# KP_Fedorov_SM5-71B.net
KiCad netlist of a schematic drawn in Altium Designer
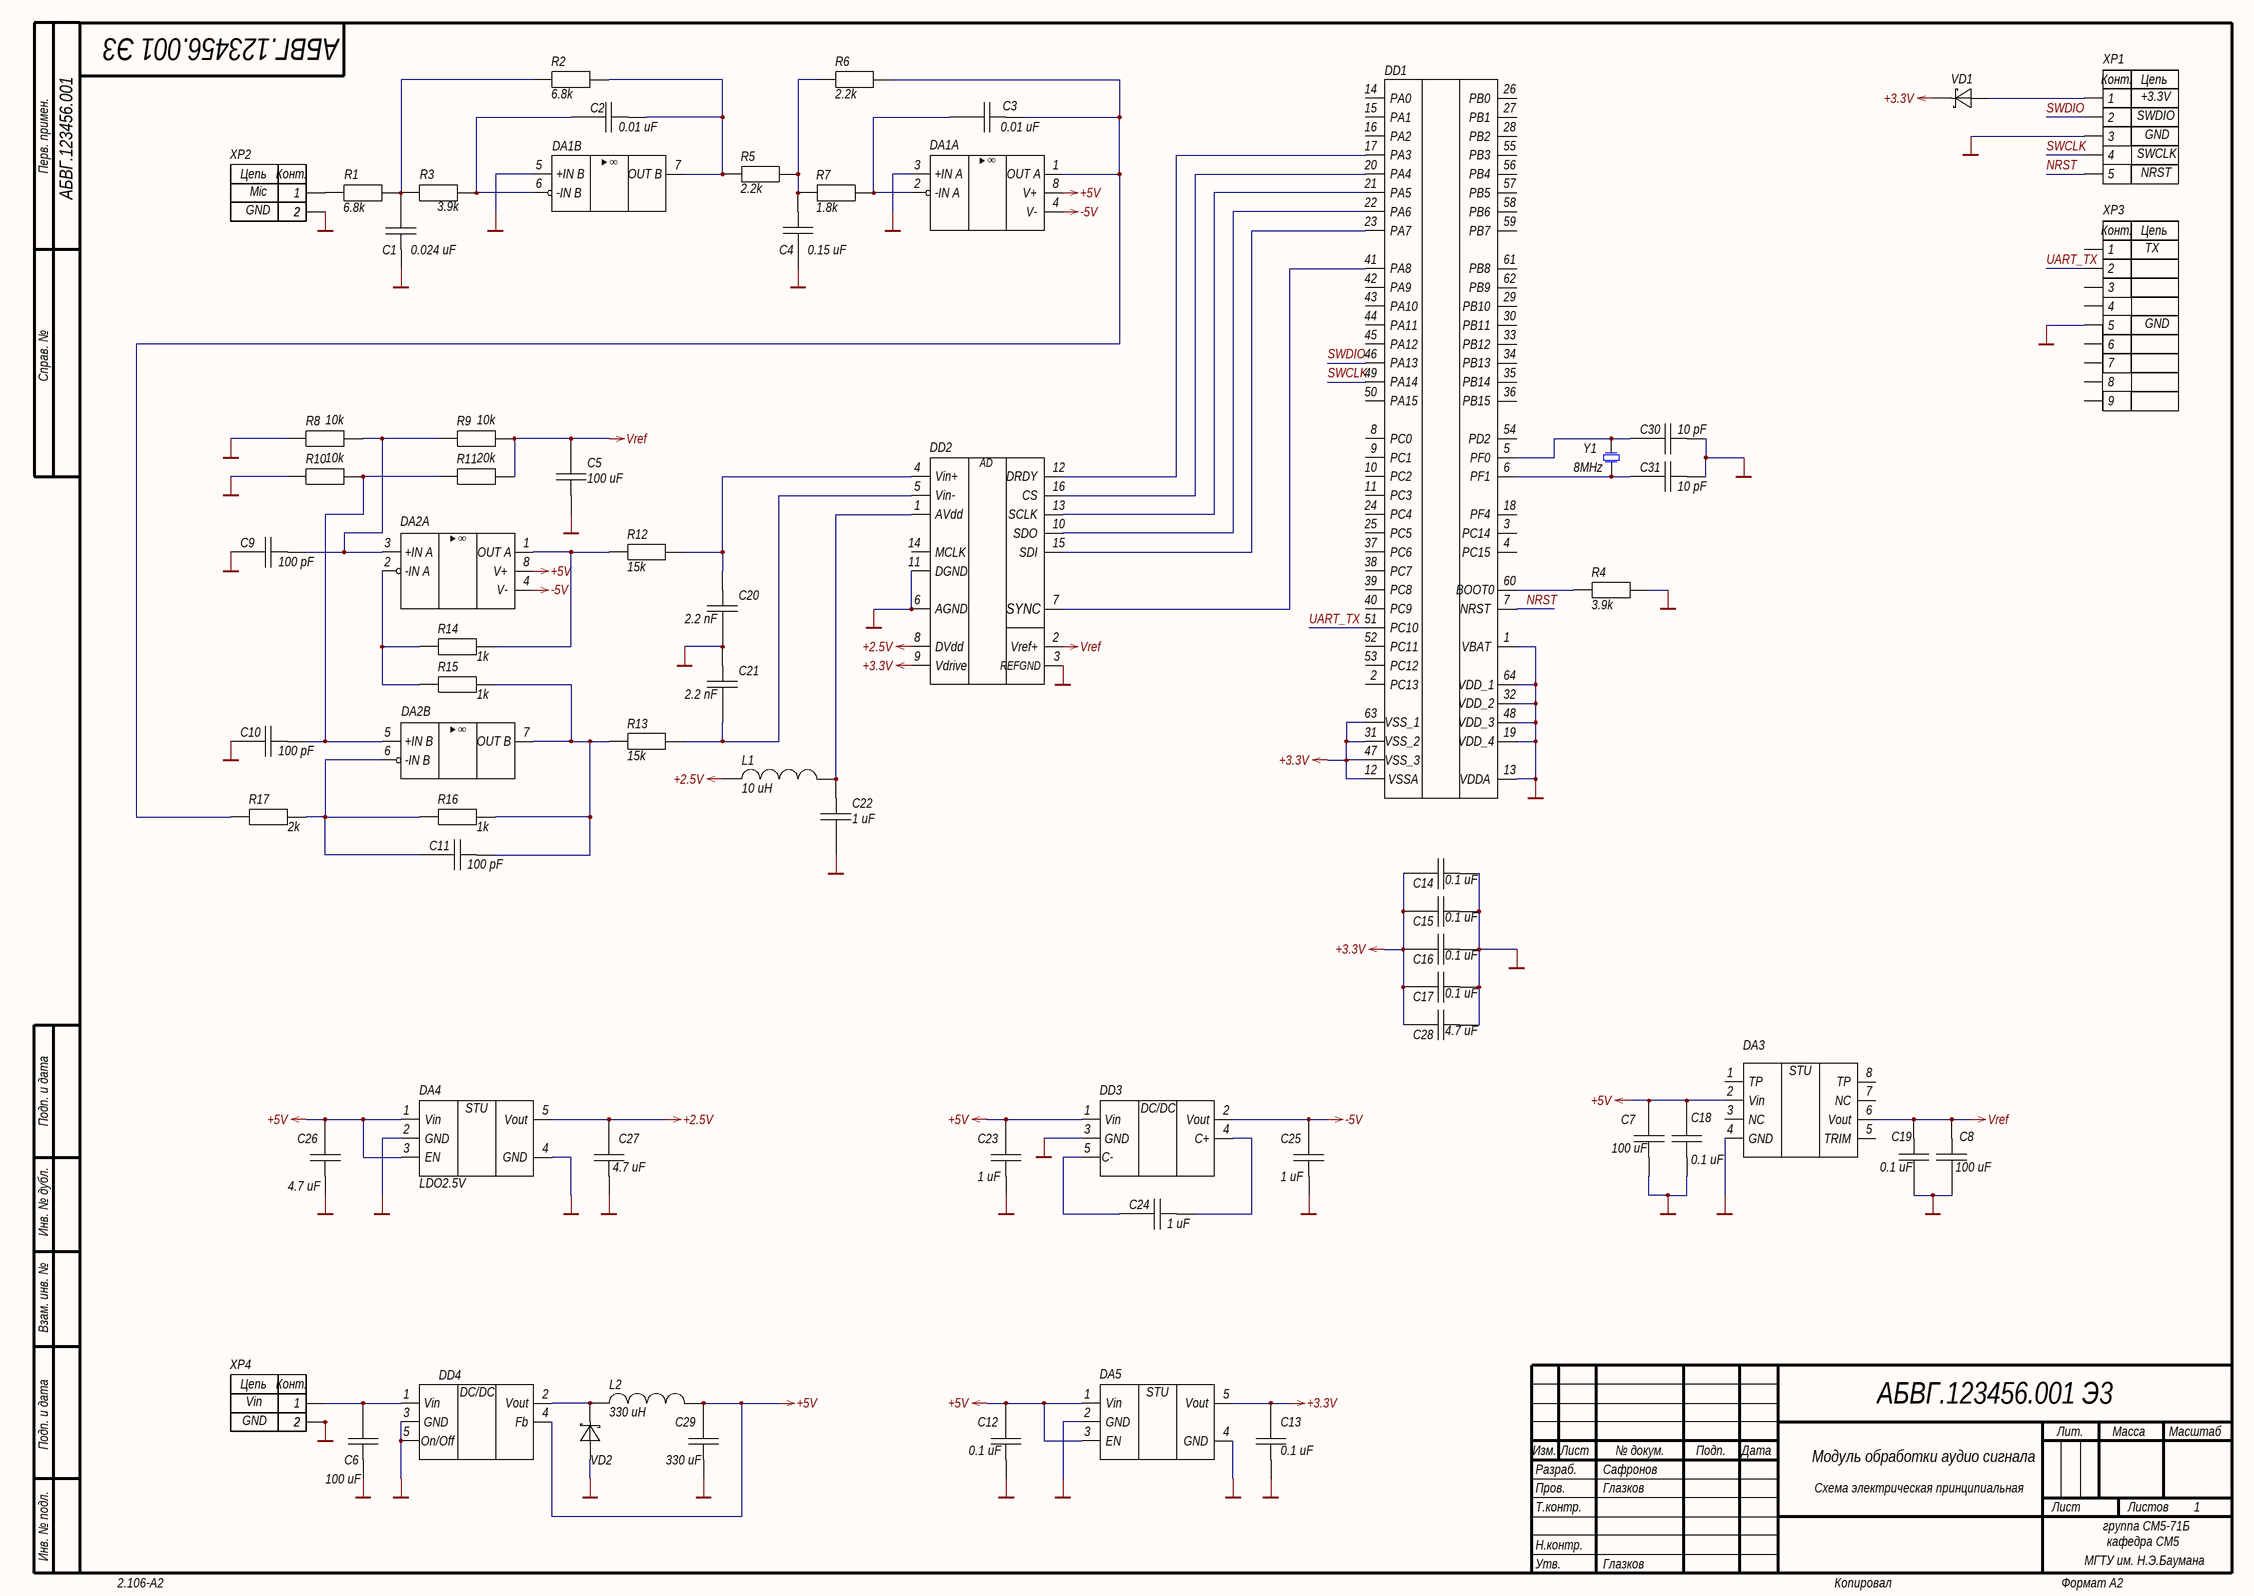
[diagram p0: KP_Fedorov_SM5-71B.SchDoc]

(export (version "E")
  (design (tool "Eeschema 10.0.6"))
  (components
    (comp (ref "C1")
      (value "0.024 uF")
      (footprint "0805 Capicator")
      (libsource (lib "KP_Fedorov_SM5-71B") (part "Capacitor"))
    )
    (comp (ref "C2")
      (value "0.01 uF")
      (footprint "0805 Capicator")
      (libsource (lib "KP_Fedorov_SM5-71B") (part "Capacitor"))
    )
    (comp (ref "C3")
      (value "0.01 uF")
      (footprint "0805 Capicator")
      (libsource (lib "KP_Fedorov_SM5-71B") (part "Capacitor"))
    )
    (comp (ref "C4")
      (value "0.15 uF")
      (footprint "0805 Capicator")
      (libsource (lib "KP_Fedorov_SM5-71B") (part "Capacitor"))
    )
    (comp (ref "C5")
      (value "100 uF")
      (footprint "0805 Capicator")
      (libsource (lib "KP_Fedorov_SM5-71B") (part "Capacitor"))
    )
    (comp (ref "C6")
      (value "100 uF")
      (footprint "0805 Capicator")
      (libsource (lib "KP_Fedorov_SM5-71B") (part "Capacitor"))
    )
    (comp (ref "C7")
      (value "100 uF")
      (footprint "0805 Capicator")
      (libsource (lib "KP_Fedorov_SM5-71B") (part "Capacitor"))
    )
    (comp (ref "C8")
      (value "100 uF")
      (footprint "0805 Capicator")
      (libsource (lib "KP_Fedorov_SM5-71B") (part "Capacitor"))
    )
    (comp (ref "C9")
      (value "100 pF")
      (footprint "0805 Capicator")
      (libsource (lib "KP_Fedorov_SM5-71B") (part "Capacitor"))
    )
    (comp (ref "C10")
      (value "100 pF")
      (footprint "0805 Capicator")
      (libsource (lib "KP_Fedorov_SM5-71B") (part "Capacitor"))
    )
    (comp (ref "C11")
      (value "100 pF")
      (footprint "0805 Capicator")
      (libsource (lib "KP_Fedorov_SM5-71B") (part "Capacitor"))
    )
    (comp (ref "C12")
      (value "0.1 uF")
      (footprint "0805 Capicator")
      (libsource (lib "KP_Fedorov_SM5-71B") (part "Capacitor"))
    )
    (comp (ref "C13")
      (value "0.1 uF")
      (footprint "0805 Capicator")
      (libsource (lib "KP_Fedorov_SM5-71B") (part "Capacitor"))
    )
    (comp (ref "C14")
      (value "0.1 uF")
      (footprint "0805 Capicator")
      (libsource (lib "KP_Fedorov_SM5-71B") (part "Capacitor"))
    )
    (comp (ref "C15")
      (value "0.1 uF")
      (footprint "0805 Capicator")
      (libsource (lib "KP_Fedorov_SM5-71B") (part "Capacitor"))
    )
    (comp (ref "C16")
      (value "0.1 uF")
      (footprint "0805 Capicator")
      (libsource (lib "KP_Fedorov_SM5-71B") (part "Capacitor"))
    )
    (comp (ref "C17")
      (value "0.1 uF")
      (footprint "0805 Capicator")
      (libsource (lib "KP_Fedorov_SM5-71B") (part "Capacitor"))
    )
    (comp (ref "C18")
      (value "0.1 uF")
      (footprint "0805 Capicator")
      (libsource (lib "KP_Fedorov_SM5-71B") (part "Capacitor"))
    )
    (comp (ref "C19")
      (value "0.1 uF")
      (footprint "0805 Capicator")
      (libsource (lib "KP_Fedorov_SM5-71B") (part "Capacitor"))
    )
    (comp (ref "C20")
      (value "2.2 nF")
      (footprint "0805 Capicator")
      (libsource (lib "KP_Fedorov_SM5-71B") (part "Capacitor"))
    )
    (comp (ref "C21")
      (value "2.2 nF")
      (footprint "0805 Capicator")
      (libsource (lib "KP_Fedorov_SM5-71B") (part "Capacitor"))
    )
    (comp (ref "C22")
      (value "1 uF")
      (footprint "0805 Capicator")
      (libsource (lib "KP_Fedorov_SM5-71B") (part "Capacitor"))
    )
    (comp (ref "C23")
      (value "1 uF")
      (footprint "0805 Capicator")
      (libsource (lib "KP_Fedorov_SM5-71B") (part "Capacitor"))
    )
    (comp (ref "C24")
      (value "1 uF")
      (footprint "0805 Capicator")
      (libsource (lib "KP_Fedorov_SM5-71B") (part "Capacitor"))
    )
    (comp (ref "C25")
      (value "1 uF")
      (footprint "0805 Capicator")
      (libsource (lib "KP_Fedorov_SM5-71B") (part "Capacitor"))
    )
    (comp (ref "C26")
      (value "4.7 uF")
      (footprint "0805 Capicator")
      (libsource (lib "KP_Fedorov_SM5-71B") (part "Capacitor"))
    )
    (comp (ref "C27")
      (value "4.7 uF")
      (footprint "0805 Capicator")
      (libsource (lib "KP_Fedorov_SM5-71B") (part "Capacitor"))
    )
    (comp (ref "C28")
      (value "4.7 uF")
      (footprint "0805 Capicator")
      (libsource (lib "KP_Fedorov_SM5-71B") (part "Capacitor"))
    )
    (comp (ref "C29")
      (value "330 uF")
      (footprint "0805 Capicator")
      (libsource (lib "KP_Fedorov_SM5-71B") (part "Capacitor"))
    )
    (comp (ref "C30")
      (value "10 pF")
      (footprint "0805 Capicator")
      (libsource (lib "KP_Fedorov_SM5-71B") (part "Capacitor"))
    )
    (comp (ref "C31")
      (value "10 pF")
      (footprint "0805 Capicator")
      (libsource (lib "KP_Fedorov_SM5-71B") (part "Capacitor"))
    )
    (comp (ref "DA1")
      (value "AD8502")
      (footprint "SOT-23-8")
      (libsource (lib "KP_Fedorov_SM5-71B") (part "OpAmp"))
    )
    (comp (ref "DA2")
      (value "AD8502")
      (footprint "SOT-23-8")
      (libsource (lib "KP_Fedorov_SM5-71B") (part "OpAmp"))
    )
    (comp (ref "DA3")
      (value "LDO")
      (footprint "SOIC-8")
      (description "ADR445BRZ")
      (libsource (lib "KP_Fedorov_SM5-71B") (part "LDO"))
    )
    (comp (ref "DA4")
      (value "LDO2.5V")
      (footprint "SOT-23-5")
      (description "ADM7160AUJZ")
      (libsource (lib "KP_Fedorov_SM5-71B") (part "LDO2.5V"))
    )
    (comp (ref "DA5")
      (value "LDO3.3V")
      (footprint "SOT-23-5")
      (description "TPS78233DDCR")
      (libsource (lib "KP_Fedorov_SM5-71B") (part "LDO3.3V"))
    )
    (comp (ref "DD1")
      (value "STM32F303RCT7")
      (footprint "LQFP64")
      (fields (field (name "MANUFACTURER") "STMicroelectronics"))
      (libsource (lib "KP_Fedorov_SM5-71B") (part "STM32F303RCT7"))
    )
    (comp (ref "DD2")
      (value "24bit 128k")
      (footprint "TSSOP-16")
      (description "AD7767")
      (libsource (lib "KP_Fedorov_SM5-71B") (part "ADC"))
    )
    (comp (ref "DD3")
      (value "DC/DC inv")
      (footprint "SOT-23-5")
      (description "TPS60403DBVR")
      (libsource (lib "KP_Fedorov_SM5-71B") (part "DC/DC inv"))
    )
    (comp (ref "DD4")
      (value "DC/DC")
      (footprint "TO-263-5L")
      (description "LM2575S-5.0/NOPB")
      (libsource (lib "KP_Fedorov_SM5-71B") (part "DC/DC"))
    )
    (comp (ref "L1")
      (value "10 uH")
      (footprint "0805 Inductor")
      (libsource (lib "KP_Fedorov_SM5-71B") (part "Inductor"))
    )
    (comp (ref "L2")
      (value "330 uH")
      (footprint "0805 Inductor")
      (libsource (lib "KP_Fedorov_SM5-71B") (part "Inductor"))
    )
    (comp (ref "R1")
      (value "6.8k")
      (footprint "0805 Resistor")
      (libsource (lib "KP_Fedorov_SM5-71B") (part "Resistor"))
    )
    (comp (ref "R2")
      (value "6.8k")
      (footprint "0805 Resistor")
      (libsource (lib "KP_Fedorov_SM5-71B") (part "Resistor"))
    )
    (comp (ref "R3")
      (value "3.9k")
      (footprint "0805 Resistor")
      (libsource (lib "KP_Fedorov_SM5-71B") (part "Resistor"))
    )
    (comp (ref "R4")
      (value "3.9k")
      (footprint "0805 Resistor")
      (libsource (lib "KP_Fedorov_SM5-71B") (part "Resistor"))
    )
    (comp (ref "R5")
      (value "2.2k")
      (footprint "0805 Resistor")
      (libsource (lib "KP_Fedorov_SM5-71B") (part "Resistor"))
    )
    (comp (ref "R6")
      (value "2.2k")
      (footprint "0805 Resistor")
      (libsource (lib "KP_Fedorov_SM5-71B") (part "Resistor"))
    )
    (comp (ref "R7")
      (value "1.8k")
      (footprint "0805 Resistor")
      (libsource (lib "KP_Fedorov_SM5-71B") (part "Resistor"))
    )
    (comp (ref "R8")
      (value "10k")
      (footprint "0805 Resistor")
      (libsource (lib "KP_Fedorov_SM5-71B") (part "Resistor"))
    )
    (comp (ref "R9")
      (value "10k")
      (footprint "0805 Resistor")
      (libsource (lib "KP_Fedorov_SM5-71B") (part "Resistor"))
    )
    (comp (ref "R10")
      (value "10k")
      (footprint "0805 Resistor")
      (libsource (lib "KP_Fedorov_SM5-71B") (part "Resistor"))
    )
    (comp (ref "R11")
      (value "20k")
      (footprint "0805 Resistor")
      (libsource (lib "KP_Fedorov_SM5-71B") (part "Resistor"))
    )
    (comp (ref "R12")
      (value "15k")
      (footprint "0805 Resistor")
      (libsource (lib "KP_Fedorov_SM5-71B") (part "Resistor"))
    )
    (comp (ref "R13")
      (value "15k")
      (footprint "0805 Resistor")
      (libsource (lib "KP_Fedorov_SM5-71B") (part "Resistor"))
    )
    (comp (ref "R14")
      (value "1k")
      (footprint "0805 Resistor")
      (libsource (lib "KP_Fedorov_SM5-71B") (part "Resistor"))
    )
    (comp (ref "R15")
      (value "1k")
      (footprint "0805 Resistor")
      (libsource (lib "KP_Fedorov_SM5-71B") (part "Resistor"))
    )
    (comp (ref "R16")
      (value "1k")
      (footprint "0805 Resistor")
      (libsource (lib "KP_Fedorov_SM5-71B") (part "Resistor"))
    )
    (comp (ref "R17")
      (value "2k")
      (footprint "0805 Resistor")
      (libsource (lib "KP_Fedorov_SM5-71B") (part "Resistor"))
    )
    (comp (ref "VD1")
      (value "MBR0520LT1G")
      (footprint "sod-123 - duplicate")
      (libsource (lib "KP_Fedorov_SM5-71B") (part "Diode Schottky"))
    )
    (comp (ref "VD2")
      (value "MBR0520LT1G")
      (footprint "sod-123 - duplicate")
      (libsource (lib "KP_Fedorov_SM5-71B") (part "Diode Schottky"))
    )
    (comp (ref "XP1")
      (value "PLS-5")
      (footprint "PBS 5x1")
      (fields (field (name "MANUFACTURER") "Amass"))
      (libsource (lib "KP_Fedorov_SM5-71B") (part "Conn5x1"))
    )
    (comp (ref "XP2")
      (value "PBS2")
      (footprint "PBS 2x1")
      (libsource (lib "KP_Fedorov_SM5-71B") (part "Conn2x1"))
    )
    (comp (ref "XP3")
      (value "SCNM9FM2MBK")
      (footprint "DB9")
      (description "DB-9M")
      (fields (field (name "PART NUMBER") "XT30PW") (field (name "MANUFACTURER") "Amass"))
      (libsource (lib "KP_Fedorov_SM5-71B") (part "Conn9x1"))
    )
    (comp (ref "XP4")
      (value "PBS2")
      (footprint "PBS 2x1")
      (libsource (lib "KP_Fedorov_SM5-71B") (part "Conn2x1"))
    )
    (comp (ref "Y1")
      (value "8MHz")
      (footprint "R38")
      (description "Crystal. HC-49S (US)")
      (fields (field (name "MANUFACTURER") "China") (field (name "PART NUMBER") "8.000MHzHC-49US"))
      (libsource (lib "BRT_baza") (part "Crystal 8MHz"))
    )
  )
  (nets
    (net (code "1") (name "+2.5V") (class "Default")
      (node (ref "C27") (pin "1") (pinfunction "1_1") (pintype "passive"))
      (node (ref "DA4") (pin "5") (pinfunction "Vout_5") (pintype "passive"))
      (node (ref "DD2") (pin "8") (pinfunction "DVdd_8") (pintype "passive"))
      (node (ref "L1") (pin "1") (pinfunction "1_1") (pintype "passive"))
    )
    (net (code "2") (name "+3.3V") (class "Default")
      (node (ref "C13") (pin "1") (pinfunction "1_1") (pintype "passive"))
      (node (ref "C14") (pin "1") (pinfunction "1_1") (pintype "passive"))
      (node (ref "C15") (pin "1") (pinfunction "1_1") (pintype "passive"))
      (node (ref "C16") (pin "1") (pinfunction "1_1") (pintype "passive"))
      (node (ref "C17") (pin "1") (pinfunction "1_1") (pintype "passive"))
      (node (ref "C28") (pin "1") (pinfunction "1_1") (pintype "passive"))
      (node (ref "DA5") (pin "5") (pinfunction "Vout_5") (pintype "passive"))
      (node (ref "DD1") (pin "12") (pinfunction "VSSA_12") (pintype "passive"))
      (node (ref "DD1") (pin "31") (pinfunction "VSS_2_31") (pintype "passive"))
      (node (ref "DD1") (pin "47") (pinfunction "VSS_3_47") (pintype "passive"))
      (node (ref "DD1") (pin "63") (pinfunction "VSS_1_63") (pintype "passive"))
      (node (ref "DD2") (pin "9") (pinfunction "Vdrive_9") (pintype "passive"))
      (node (ref "VD1") (pin "2") (pinfunction "2_2") (pintype "passive"))
    )
    (net (code "3") (name "+5V") (class "Default")
      (node (ref "C12") (pin "1") (pinfunction "1_1") (pintype "passive"))
      (node (ref "C18") (pin "1") (pinfunction "1_1") (pintype "passive"))
      (node (ref "C23") (pin "1") (pinfunction "1_1") (pintype "passive"))
      (node (ref "C26") (pin "1") (pinfunction "1_1") (pintype "passive"))
      (node (ref "C29") (pin "1") (pinfunction "1_1") (pintype "passive"))
      (node (ref "C7") (pin "1") (pinfunction "1_1") (pintype "passive"))
      (node (ref "DA1") (pin "8") (pinfunction "V+_8") (pintype "passive"))
      (node (ref "DA2") (pin "8") (pinfunction "V+_8") (pintype "passive"))
      (node (ref "DA3") (pin "2") (pinfunction "Vin_2") (pintype "passive"))
      (node (ref "DA4") (pin "1") (pinfunction "Vin_1") (pintype "passive"))
      (node (ref "DA4") (pin "3") (pinfunction "EN_3") (pintype "passive"))
      (node (ref "DA5") (pin "1") (pinfunction "Vin_1") (pintype "passive"))
      (node (ref "DA5") (pin "3") (pinfunction "EN_3") (pintype "passive"))
      (node (ref "DD3") (pin "1") (pinfunction "Vin_1") (pintype "power_in"))
      (node (ref "DD4") (pin "4") (pinfunction "Fb_4") (pintype "passive"))
      (node (ref "L2") (pin "2") (pinfunction "2_2") (pintype "passive"))
    )
    (net (code "4") (name "-5V") (class "Default")
      (node (ref "C25") (pin "1") (pinfunction "1_1") (pintype "passive"))
      (node (ref "DA1") (pin "4") (pinfunction "V-_4") (pintype "passive"))
      (node (ref "DA2") (pin "4") (pinfunction "V-_4") (pintype "passive"))
      (node (ref "DD3") (pin "2") (pinfunction "Vout_2") (pintype "passive"))
    )
    (net (code "5") (name "/NRST") (class "Default")
      (node (ref "DD1") (pin "7") (pinfunction "NRST_7") (pintype "passive"))
      (node (ref "XP1") (pin "5") (pinfunction "5_5") (pintype "passive"))
    )
    (net (code "6") (name "/SWCLK") (class "Default")
      (node (ref "DD1") (pin "49") (pinfunction "PA14_49") (pintype "passive"))
      (node (ref "XP1") (pin "4") (pinfunction "4_4") (pintype "passive"))
    )
    (net (code "7") (name "/SWDIO") (class "Default")
      (node (ref "DD1") (pin "46") (pinfunction "PA13_46") (pintype "passive"))
      (node (ref "XP1") (pin "2") (pinfunction "2_2") (pintype "passive"))
    )
    (net (code "8") (name "/UART_TX") (class "Default")
      (node (ref "DD1") (pin "51") (pinfunction "PC10_51") (pintype "passive"))
      (node (ref "XP3") (pin "2") (pinfunction "2_2") (pintype "passive"))
    )
    (net (code "9") (name "GND") (class "Default")
      (node (ref "C1") (pin "2") (pinfunction "2_2") (pintype "passive"))
      (node (ref "C10") (pin "1") (pinfunction "1_1") (pintype "passive"))
      (node (ref "C12") (pin "2") (pinfunction "2_2") (pintype "passive"))
      (node (ref "C13") (pin "2") (pinfunction "2_2") (pintype "passive"))
      (node (ref "C14") (pin "2") (pinfunction "2_2") (pintype "passive"))
      (node (ref "C15") (pin "2") (pinfunction "2_2") (pintype "passive"))
      (node (ref "C16") (pin "2") (pinfunction "2_2") (pintype "passive"))
      (node (ref "C17") (pin "2") (pinfunction "2_2") (pintype "passive"))
      (node (ref "C18") (pin "2") (pinfunction "2_2") (pintype "passive"))
      (node (ref "C19") (pin "1") (pinfunction "1_1") (pintype "passive"))
      (node (ref "C20") (pin "1") (pinfunction "1_1") (pintype "passive"))
      (node (ref "C21") (pin "2") (pinfunction "2_2") (pintype "passive"))
      (node (ref "C22") (pin "1") (pinfunction "1_1") (pintype "passive"))
      (node (ref "C23") (pin "2") (pinfunction "2_2") (pintype "passive"))
      (node (ref "C25") (pin "2") (pinfunction "2_2") (pintype "passive"))
      (node (ref "C26") (pin "2") (pinfunction "2_2") (pintype "passive"))
      (node (ref "C27") (pin "2") (pinfunction "2_2") (pintype "passive"))
      (node (ref "C28") (pin "2") (pinfunction "2_2") (pintype "passive"))
      (node (ref "C29") (pin "2") (pinfunction "2_2") (pintype "passive"))
      (node (ref "C30") (pin "2") (pinfunction "2_2") (pintype "passive"))
      (node (ref "C31") (pin "2") (pinfunction "2_2") (pintype "passive"))
      (node (ref "C4") (pin "1") (pinfunction "1_1") (pintype "passive"))
      (node (ref "C5") (pin "2") (pinfunction "2_2") (pintype "passive"))
      (node (ref "C6") (pin "2") (pinfunction "2_2") (pintype "passive"))
      (node (ref "C7") (pin "2") (pinfunction "2_2") (pintype "passive"))
      (node (ref "C8") (pin "1") (pinfunction "1_1") (pintype "passive"))
      (node (ref "C9") (pin "1") (pinfunction "1_1") (pintype "passive"))
      (node (ref "DA1") (pin "3") (pinfunction "+IN_A_3") (pintype "passive"))
      (node (ref "DA1") (pin "5") (pinfunction "+IN_B_5") (pintype "passive"))
      (node (ref "DA3") (pin "4") (pinfunction "GND_4") (pintype "passive"))
      (node (ref "DA4") (pin "2") (pinfunction "GND_2") (pintype "passive"))
      (node (ref "DA4") (pin "4") (pinfunction "GND_4") (pintype "passive"))
      (node (ref "DA5") (pin "2") (pinfunction "GND_2") (pintype "passive"))
      (node (ref "DA5") (pin "4") (pinfunction "GND_4") (pintype "passive"))
      (node (ref "DD1") (pin "1") (pinfunction "VBAT_1") (pintype "passive"))
      (node (ref "DD1") (pin "13") (pinfunction "VDDA_13") (pintype "passive"))
      (node (ref "DD1") (pin "19") (pinfunction "VDD_4_19") (pintype "passive"))
      (node (ref "DD1") (pin "32") (pinfunction "VDD_2_32") (pintype "passive"))
      (node (ref "DD1") (pin "48") (pinfunction "VDD_3_48") (pintype "passive"))
      (node (ref "DD1") (pin "64") (pinfunction "VDD_1_64") (pintype "passive"))
      (node (ref "DD2") (pin "11") (pinfunction "DGND_11") (pintype "passive"))
      (node (ref "DD2") (pin "3") (pinfunction "REFGND_3") (pintype "passive"))
      (node (ref "DD2") (pin "6") (pinfunction "AGND_6") (pintype "passive"))
      (node (ref "DD3") (pin "3") (pinfunction "GND_3") (pintype "power_in"))
      (node (ref "DD4") (pin "3") (pinfunction "GND_3") (pintype "power_in"))
      (node (ref "DD4") (pin "5") (pinfunction "On/Off_5") (pintype "power_in"))
      (node (ref "R10") (pin "1") (pinfunction "1_1") (pintype "passive"))
      (node (ref "R4") (pin "2") (pinfunction "2_2") (pintype "passive"))
      (node (ref "R8") (pin "1") (pinfunction "1_1") (pintype "passive"))
      (node (ref "VD2") (pin "1") (pinfunction "1_1") (pintype "passive"))
      (node (ref "XP1") (pin "3") (pinfunction "3_3") (pintype "passive"))
      (node (ref "XP2") (pin "2") (pinfunction "2_2") (pintype "passive"))
      (node (ref "XP3") (pin "5") (pinfunction "5_5") (pintype "passive"))
      (node (ref "XP4") (pin "2") (pinfunction "2_2") (pintype "passive"))
    )
    (net (code "10") (name "Net-(C1-Pad1)") (class "Default")
      (node (ref "C1") (pin "1") (pinfunction "1_1") (pintype "passive"))
      (node (ref "R1") (pin "2") (pinfunction "2_2") (pintype "passive"))
      (node (ref "R2") (pin "1") (pinfunction "1_1") (pintype "passive"))
      (node (ref "R3") (pin "1") (pinfunction "1_1") (pintype "passive"))
    )
    (net (code "11") (name "Net-(C4-Pad2)") (class "Default")
      (node (ref "C4") (pin "2") (pinfunction "2_2") (pintype "passive"))
      (node (ref "R5") (pin "1") (pinfunction "1_1") (pintype "passive"))
      (node (ref "R6") (pin "1") (pinfunction "1_1") (pintype "passive"))
      (node (ref "R7") (pin "2") (pinfunction "2_2") (pintype "passive"))
    )
    (net (code "12") (name "Net-(DA1A--IN_A)") (class "Default")
      (node (ref "C3") (pin "1") (pinfunction "1_1") (pintype "passive"))
      (node (ref "DA1") (pin "2") (pinfunction "-IN_A_2") (pintype "passive"))
      (node (ref "R7") (pin "1") (pinfunction "1_1") (pintype "passive"))
    )
    (net (code "13") (name "Net-(DA1A-OUT_A)") (class "Default")
      (node (ref "C3") (pin "2") (pinfunction "2_2") (pintype "passive"))
      (node (ref "DA1") (pin "1") (pinfunction "OUT_A_1") (pintype "passive"))
      (node (ref "R17") (pin "1") (pinfunction "1_1") (pintype "passive"))
      (node (ref "R6") (pin "2") (pinfunction "2_2") (pintype "passive"))
    )
    (net (code "14") (name "Net-(DA1B--IN_B)") (class "Default")
      (node (ref "C2") (pin "1") (pinfunction "1_1") (pintype "passive"))
      (node (ref "DA1") (pin "6") (pinfunction "-IN_B_6") (pintype "passive"))
      (node (ref "R3") (pin "2") (pinfunction "2_2") (pintype "passive"))
    )
    (net (code "15") (name "Net-(DA1B-OUT_B)") (class "Default")
      (node (ref "C2") (pin "2") (pinfunction "2_2") (pintype "passive"))
      (node (ref "DA1") (pin "7") (pinfunction "OUT_B_7") (pintype "passive"))
      (node (ref "R2") (pin "2") (pinfunction "2_2") (pintype "passive"))
      (node (ref "R5") (pin "2") (pinfunction "2_2") (pintype "passive"))
    )
    (net (code "16") (name "Net-(DA2A-+IN_A)") (class "Default")
      (node (ref "C9") (pin "2") (pinfunction "2_2") (pintype "passive"))
      (node (ref "DA2") (pin "3") (pinfunction "+IN_A_3") (pintype "passive"))
      (node (ref "R8") (pin "2") (pinfunction "2_2") (pintype "passive"))
      (node (ref "R9") (pin "1") (pinfunction "1_1") (pintype "passive"))
    )
    (net (code "17") (name "Net-(DA2A--IN_A)") (class "Default")
      (node (ref "DA2") (pin "2") (pinfunction "-IN_A_2") (pintype "passive"))
      (node (ref "R14") (pin "1") (pinfunction "1_1") (pintype "passive"))
      (node (ref "R15") (pin "1") (pinfunction "1_1") (pintype "passive"))
    )
    (net (code "18") (name "Net-(DA2A-OUT_A)") (class "Default")
      (node (ref "DA2") (pin "1") (pinfunction "OUT_A_1") (pintype "passive"))
      (node (ref "R12") (pin "1") (pinfunction "1_1") (pintype "passive"))
      (node (ref "R14") (pin "2") (pinfunction "2_2") (pintype "passive"))
    )
    (net (code "19") (name "Net-(DA2B-+IN_B)") (class "Default")
      (node (ref "C10") (pin "2") (pinfunction "2_2") (pintype "passive"))
      (node (ref "DA2") (pin "5") (pinfunction "+IN_B_5") (pintype "passive"))
      (node (ref "R10") (pin "2") (pinfunction "2_2") (pintype "passive"))
      (node (ref "R11") (pin "1") (pinfunction "1_1") (pintype "passive"))
    )
    (net (code "20") (name "Net-(DA2B--IN_B)") (class "Default")
      (node (ref "C11") (pin "1") (pinfunction "1_1") (pintype "passive"))
      (node (ref "DA2") (pin "6") (pinfunction "-IN_B_6") (pintype "passive"))
      (node (ref "R16") (pin "1") (pinfunction "1_1") (pintype "passive"))
      (node (ref "R17") (pin "2") (pinfunction "2_2") (pintype "passive"))
    )
    (net (code "21") (name "Net-(DA2B-OUT_B)") (class "Default")
      (node (ref "C11") (pin "2") (pinfunction "2_2") (pintype "passive"))
      (node (ref "DA2") (pin "7") (pinfunction "OUT_B_7") (pintype "passive"))
      (node (ref "R13") (pin "1") (pinfunction "1_1") (pintype "passive"))
      (node (ref "R15") (pin "2") (pinfunction "2_2") (pintype "passive"))
      (node (ref "R16") (pin "2") (pinfunction "2_2") (pintype "passive"))
    )
    (net (code "22") (name "Net-(DD1-BOOT0)") (class "Default")
      (node (ref "DD1") (pin "60") (pinfunction "BOOT0_60") (pintype "passive"))
      (node (ref "R4") (pin "1") (pinfunction "1_1") (pintype "passive"))
    )
    (net (code "23") (name "Net-(DD1-PA3)") (class "Default")
      (node (ref "DD1") (pin "17") (pinfunction "PA3_17") (pintype "passive"))
      (node (ref "DD2") (pin "12") (pinfunction "DRDY_12") (pintype "passive"))
    )
    (net (code "24") (name "Net-(DD1-PA4)") (class "Default")
      (node (ref "DD1") (pin "20") (pinfunction "PA4_20") (pintype "passive"))
      (node (ref "DD2") (pin "16") (pinfunction "CS_16") (pintype "passive"))
    )
    (net (code "25") (name "Net-(DD1-PA5)") (class "Default")
      (node (ref "DD1") (pin "21") (pinfunction "PA5_21") (pintype "passive"))
      (node (ref "DD2") (pin "13") (pinfunction "SCLK_13") (pintype "passive"))
    )
    (net (code "26") (name "Net-(DD1-PA6)") (class "Default")
      (node (ref "DD1") (pin "22") (pinfunction "PA6_22") (pintype "passive"))
      (node (ref "DD2") (pin "10") (pinfunction "SDO_10") (pintype "passive"))
    )
    (net (code "27") (name "Net-(DD1-PA7)") (class "Default")
      (node (ref "DD1") (pin "23") (pinfunction "PA7_23") (pintype "passive"))
      (node (ref "DD2") (pin "15") (pinfunction "SDI_15") (pintype "passive"))
    )
    (net (code "28") (name "Net-(DD1-PA8)") (class "Default")
      (node (ref "DD1") (pin "41") (pinfunction "PA8_41") (pintype "passive"))
      (node (ref "DD2") (pin "7") (pinfunction "SYNC_7") (pintype "passive"))
    )
    (net (code "29") (name "Net-(DD1-PF0)") (class "Default")
      (node (ref "C30") (pin "1") (pinfunction "1_1") (pintype "passive"))
      (node (ref "DD1") (pin "5") (pinfunction "PF0_5") (pintype "passive"))
      (node (ref "Y1") (pin "1") (pinfunction "1_1") (pintype "passive"))
    )
    (net (code "30") (name "Net-(DD1-PF1)") (class "Default")
      (node (ref "C31") (pin "1") (pinfunction "1_1") (pintype "passive"))
      (node (ref "DD1") (pin "6") (pinfunction "PF1_6") (pintype "passive"))
      (node (ref "Y1") (pin "2") (pinfunction "2_2") (pintype "passive"))
    )
    (net (code "31") (name "Net-(DD2-AVdd)") (class "Default")
      (node (ref "C22") (pin "2") (pinfunction "2_2") (pintype "passive"))
      (node (ref "DD2") (pin "1") (pinfunction "AVdd_1") (pintype "passive"))
      (node (ref "L1") (pin "2") (pinfunction "2_2") (pintype "passive"))
    )
    (net (code "32") (name "Net-(DD2-Vin+)") (class "Default")
      (node (ref "C20") (pin "2") (pinfunction "2_2") (pintype "passive"))
      (node (ref "DD2") (pin "4") (pinfunction "Vin+_4") (pintype "passive"))
      (node (ref "R12") (pin "2") (pinfunction "2_2") (pintype "passive"))
    )
    (net (code "33") (name "Net-(DD2-Vin-)") (class "Default")
      (node (ref "C21") (pin "1") (pinfunction "1_1") (pintype "passive"))
      (node (ref "DD2") (pin "5") (pinfunction "Vin-_5") (pintype "passive"))
      (node (ref "R13") (pin "2") (pinfunction "2_2") (pintype "passive"))
    )
    (net (code "34") (name "Net-(DD3-C+)") (class "Default")
      (node (ref "C24") (pin "2") (pinfunction "2_2") (pintype "passive"))
      (node (ref "DD3") (pin "4") (pinfunction "C+_4") (pintype "passive"))
    )
    (net (code "35") (name "Net-(DD3-C-)") (class "Default")
      (node (ref "C24") (pin "1") (pinfunction "1_1") (pintype "passive"))
      (node (ref "DD3") (pin "5") (pinfunction "C-_5") (pintype "power_in"))
    )
    (net (code "36") (name "Net-(DD4-Vin)") (class "Default")
      (node (ref "C6") (pin "1") (pinfunction "1_1") (pintype "passive"))
      (node (ref "DD4") (pin "1") (pinfunction "Vin_1") (pintype "power_in"))
      (node (ref "XP4") (pin "1") (pinfunction "1_1") (pintype "passive"))
    )
    (net (code "37") (name "Net-(DD4-Vout)") (class "Default")
      (node (ref "DD4") (pin "2") (pinfunction "Vout_2") (pintype "passive"))
      (node (ref "L2") (pin "1") (pinfunction "1_1") (pintype "passive"))
      (node (ref "VD2") (pin "2") (pinfunction "2_2") (pintype "passive"))
    )
    (net (code "38") (name "Net-(R1-Pad1)") (class "Default")
      (node (ref "R1") (pin "1") (pinfunction "1_1") (pintype "passive"))
      (node (ref "XP2") (pin "1") (pinfunction "1_1") (pintype "passive"))
    )
    (net (code "39") (name "Net-(VD1-Pad1)") (class "Default")
      (node (ref "VD1") (pin "1") (pinfunction "1_1") (pintype "passive"))
      (node (ref "XP1") (pin "1") (pinfunction "1_1") (pintype "passive"))
    )
    (net (code "40") (name "Vref") (class "Default")
      (node (ref "C19") (pin "2") (pinfunction "2_2") (pintype "passive"))
      (node (ref "C5") (pin "1") (pinfunction "1_1") (pintype "passive"))
      (node (ref "C8") (pin "2") (pinfunction "2_2") (pintype "passive"))
      (node (ref "DA3") (pin "6") (pinfunction "Vout_6") (pintype "passive"))
      (node (ref "DD2") (pin "2") (pinfunction "Vref+_2") (pintype "passive"))
      (node (ref "R11") (pin "2") (pinfunction "2_2") (pintype "passive"))
      (node (ref "R9") (pin "2") (pinfunction "2_2") (pintype "passive"))
    )
    (net (code "41") (name "unconnected-(DA3-NC-Pad3)") (class "Default")
      (node (ref "DA3") (pin "3") (pinfunction "NC_3") (pintype "passive"))
    )
    (net (code "42") (name "unconnected-(DA3-NC-Pad7)") (class "Default")
      (node (ref "DA3") (pin "7") (pinfunction "NC_7") (pintype "passive"))
    )
    (net (code "43") (name "unconnected-(DA3-TP-Pad1)") (class "Default")
      (node (ref "DA3") (pin "1") (pinfunction "TP_1") (pintype "passive"))
    )
    (net (code "44") (name "unconnected-(DA3-TP-Pad8)") (class "Default")
      (node (ref "DA3") (pin "8") (pinfunction "TP_8") (pintype "passive"))
    )
    (net (code "45") (name "unconnected-(DA3-TRIM-Pad5)") (class "Default")
      (node (ref "DA3") (pin "5") (pinfunction "TRIM_5") (pintype "passive"))
    )
    (net (code "46") (name "unconnected-(DD1-PA0-Pad14)") (class "Default")
      (node (ref "DD1") (pin "14") (pinfunction "PA0_14") (pintype "passive"))
    )
    (net (code "47") (name "unconnected-(DD1-PA1-Pad15)") (class "Default")
      (node (ref "DD1") (pin "15") (pinfunction "PA1_15") (pintype "passive"))
    )
    (net (code "48") (name "unconnected-(DD1-PA2-Pad16)") (class "Default")
      (node (ref "DD1") (pin "16") (pinfunction "PA2_16") (pintype "passive"))
    )
    (net (code "49") (name "unconnected-(DD1-PA9-Pad42)") (class "Default")
      (node (ref "DD1") (pin "42") (pinfunction "PA9_42") (pintype "passive"))
    )
    (net (code "50") (name "unconnected-(DD1-PA10-Pad43)") (class "Default")
      (node (ref "DD1") (pin "43") (pinfunction "PA10_43") (pintype "passive"))
    )
    (net (code "51") (name "unconnected-(DD1-PA11-Pad44)") (class "Default")
      (node (ref "DD1") (pin "44") (pinfunction "PA11_44") (pintype "passive"))
    )
    (net (code "52") (name "unconnected-(DD1-PA12-Pad45)") (class "Default")
      (node (ref "DD1") (pin "45") (pinfunction "PA12_45") (pintype "passive"))
    )
    (net (code "53") (name "unconnected-(DD1-PA15-Pad50)") (class "Default")
      (node (ref "DD1") (pin "50") (pinfunction "PA15_50") (pintype "passive"))
    )
    (net (code "54") (name "unconnected-(DD1-PB0-Pad26)") (class "Default")
      (node (ref "DD1") (pin "26") (pinfunction "PB0_26") (pintype "passive"))
    )
    (net (code "55") (name "unconnected-(DD1-PB1-Pad27)") (class "Default")
      (node (ref "DD1") (pin "27") (pinfunction "PB1_27") (pintype "passive"))
    )
    (net (code "56") (name "unconnected-(DD1-PB2-Pad28)") (class "Default")
      (node (ref "DD1") (pin "28") (pinfunction "PB2_28") (pintype "passive"))
    )
    (net (code "57") (name "unconnected-(DD1-PB3-Pad55)") (class "Default")
      (node (ref "DD1") (pin "55") (pinfunction "PB3_55") (pintype "passive"))
    )
    (net (code "58") (name "unconnected-(DD1-PB4-Pad56)") (class "Default")
      (node (ref "DD1") (pin "56") (pinfunction "PB4_56") (pintype "passive"))
    )
    (net (code "59") (name "unconnected-(DD1-PB5-Pad57)") (class "Default")
      (node (ref "DD1") (pin "57") (pinfunction "PB5_57") (pintype "passive"))
    )
    (net (code "60") (name "unconnected-(DD1-PB6-Pad58)") (class "Default")
      (node (ref "DD1") (pin "58") (pinfunction "PB6_58") (pintype "passive"))
    )
    (net (code "61") (name "unconnected-(DD1-PB7-Pad59)") (class "Default")
      (node (ref "DD1") (pin "59") (pinfunction "PB7_59") (pintype "passive"))
    )
    (net (code "62") (name "unconnected-(DD1-PB8-Pad61)") (class "Default")
      (node (ref "DD1") (pin "61") (pinfunction "PB8_61") (pintype "passive"))
    )
    (net (code "63") (name "unconnected-(DD1-PB9-Pad62)") (class "Default")
      (node (ref "DD1") (pin "62") (pinfunction "PB9_62") (pintype "passive"))
    )
    (net (code "64") (name "unconnected-(DD1-PB10-Pad29)") (class "Default")
      (node (ref "DD1") (pin "29") (pinfunction "PB10_29") (pintype "passive"))
    )
    (net (code "65") (name "unconnected-(DD1-PB11-Pad30)") (class "Default")
      (node (ref "DD1") (pin "30") (pinfunction "PB11_30") (pintype "passive"))
    )
    (net (code "66") (name "unconnected-(DD1-PB12-Pad33)") (class "Default")
      (node (ref "DD1") (pin "33") (pinfunction "PB12_33") (pintype "passive"))
    )
    (net (code "67") (name "unconnected-(DD1-PB13-Pad34)") (class "Default")
      (node (ref "DD1") (pin "34") (pinfunction "PB13_34") (pintype "passive"))
    )
    (net (code "68") (name "unconnected-(DD1-PB14-Pad35)") (class "Default")
      (node (ref "DD1") (pin "35") (pinfunction "PB14_35") (pintype "passive"))
    )
    (net (code "69") (name "unconnected-(DD1-PB15-Pad36)") (class "Default")
      (node (ref "DD1") (pin "36") (pinfunction "PB15_36") (pintype "passive"))
    )
    (net (code "70") (name "unconnected-(DD1-PC0-Pad8)") (class "Default")
      (node (ref "DD1") (pin "8") (pinfunction "PC0_8") (pintype "passive"))
    )
    (net (code "71") (name "unconnected-(DD1-PC1-Pad9)") (class "Default")
      (node (ref "DD1") (pin "9") (pinfunction "PC1_9") (pintype "passive"))
    )
    (net (code "72") (name "unconnected-(DD1-PC2-Pad10)") (class "Default")
      (node (ref "DD1") (pin "10") (pinfunction "PC2_10") (pintype "passive"))
    )
    (net (code "73") (name "unconnected-(DD1-PC3-Pad11)") (class "Default")
      (node (ref "DD1") (pin "11") (pinfunction "PC3_11") (pintype "passive"))
    )
    (net (code "74") (name "unconnected-(DD1-PC4-Pad24)") (class "Default")
      (node (ref "DD1") (pin "24") (pinfunction "PC4_24") (pintype "passive"))
    )
    (net (code "75") (name "unconnected-(DD1-PC5-Pad25)") (class "Default")
      (node (ref "DD1") (pin "25") (pinfunction "PC5_25") (pintype "passive"))
    )
    (net (code "76") (name "unconnected-(DD1-PC6-Pad37)") (class "Default")
      (node (ref "DD1") (pin "37") (pinfunction "PC6_37") (pintype "passive"))
    )
    (net (code "77") (name "unconnected-(DD1-PC7-Pad38)") (class "Default")
      (node (ref "DD1") (pin "38") (pinfunction "PC7_38") (pintype "passive"))
    )
    (net (code "78") (name "unconnected-(DD1-PC8-Pad39)") (class "Default")
      (node (ref "DD1") (pin "39") (pinfunction "PC8_39") (pintype "passive"))
    )
    (net (code "79") (name "unconnected-(DD1-PC9-Pad40)") (class "Default")
      (node (ref "DD1") (pin "40") (pinfunction "PC9_40") (pintype "passive"))
    )
    (net (code "80") (name "unconnected-(DD1-PC11-Pad52)") (class "Default")
      (node (ref "DD1") (pin "52") (pinfunction "PC11_52") (pintype "passive"))
    )
    (net (code "81") (name "unconnected-(DD1-PC12-Pad53)") (class "Default")
      (node (ref "DD1") (pin "53") (pinfunction "PC12_53") (pintype "passive"))
    )
    (net (code "82") (name "unconnected-(DD1-PC13-Pad2)") (class "Default")
      (node (ref "DD1") (pin "2") (pinfunction "PC13_2") (pintype "passive"))
    )
    (net (code "83") (name "unconnected-(DD1-PC14-Pad3)") (class "Default")
      (node (ref "DD1") (pin "3") (pinfunction "PC14_3") (pintype "passive"))
    )
    (net (code "84") (name "unconnected-(DD1-PC15-Pad4)") (class "Default")
      (node (ref "DD1") (pin "4") (pinfunction "PC15_4") (pintype "passive"))
    )
    (net (code "85") (name "unconnected-(DD1-PD2-Pad54)") (class "Default")
      (node (ref "DD1") (pin "54") (pinfunction "PD2_54") (pintype "passive"))
    )
    (net (code "86") (name "unconnected-(DD1-PF4-Pad18)") (class "Default")
      (node (ref "DD1") (pin "18") (pinfunction "PF4_18") (pintype "passive"))
    )
    (net (code "87") (name "unconnected-(DD2-MCLK-Pad14)") (class "Default")
      (node (ref "DD2") (pin "14") (pinfunction "MCLK_14") (pintype "passive"))
    )
    (net (code "88") (name "unconnected-(XP3-Pad1)") (class "Default")
      (node (ref "XP3") (pin "1") (pinfunction "1_1") (pintype "passive"))
    )
    (net (code "89") (name "unconnected-(XP3-Pad3)") (class "Default")
      (node (ref "XP3") (pin "3") (pinfunction "3_3") (pintype "passive"))
    )
    (net (code "90") (name "unconnected-(XP3-Pad4)") (class "Default")
      (node (ref "XP3") (pin "4") (pinfunction "4_4") (pintype "passive"))
    )
    (net (code "91") (name "unconnected-(XP3-Pad6)") (class "Default")
      (node (ref "XP3") (pin "6") (pinfunction "6_6") (pintype "passive"))
    )
    (net (code "92") (name "unconnected-(XP3-Pad7)") (class "Default")
      (node (ref "XP3") (pin "7") (pinfunction "7_7") (pintype "passive"))
    )
    (net (code "93") (name "unconnected-(XP3-Pad8)") (class "Default")
      (node (ref "XP3") (pin "8") (pinfunction "8_8") (pintype "passive"))
    )
    (net (code "94") (name "unconnected-(XP3-Pad9)") (class "Default")
      (node (ref "XP3") (pin "9") (pinfunction "9_9") (pintype "passive"))
    )
  )
)
